# V9938.net
KiCad netlist of a schematic drawn in EAGLE
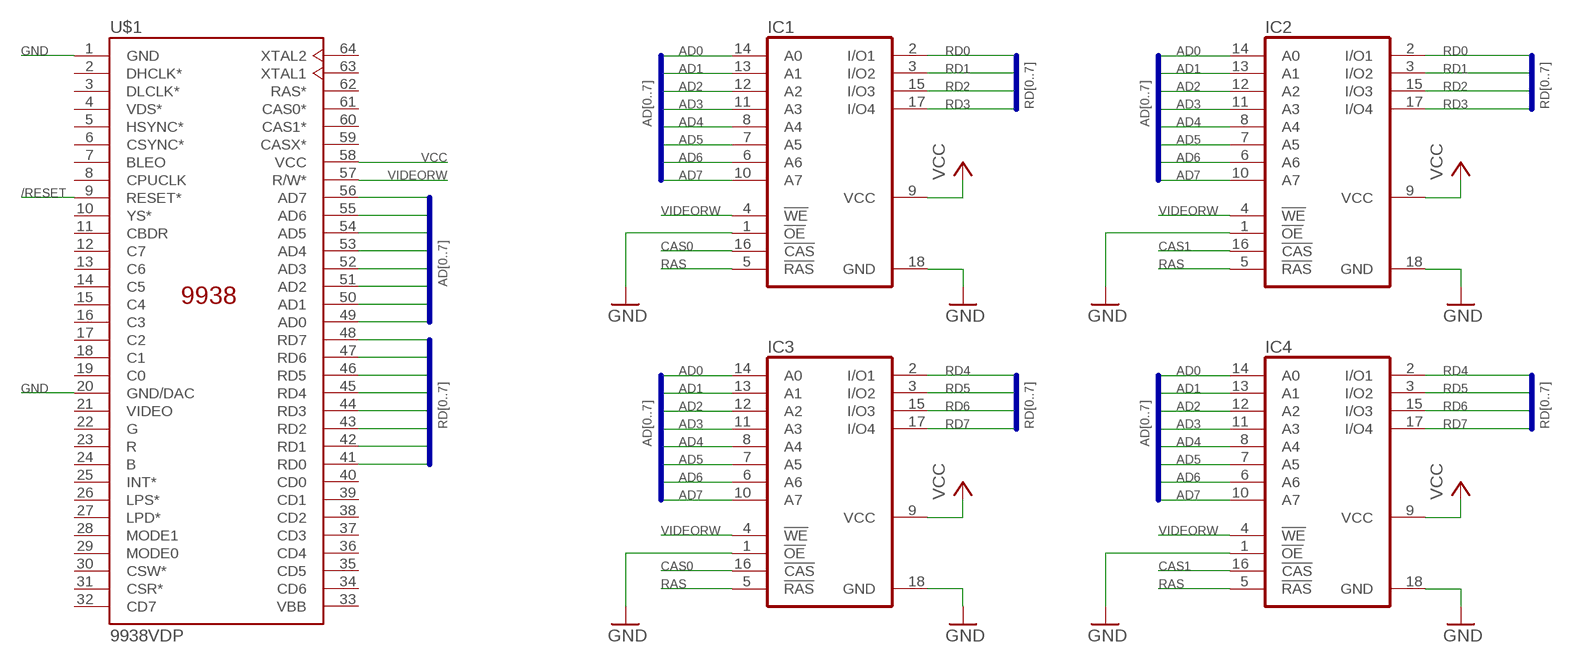
[diagram p0: schematic, sheet 1]

(export (version "E")
  (design (tool "Eeschema 10.0.6"))
  (components
    (comp (ref "IC1")
      (value "41464C")
      (footprint "eagle-import:DIL18")
      (libsource (lib "eagle-import") (part "41464C"))
    )
    (comp (ref "IC2")
      (value "41464C")
      (footprint "eagle-import:DIL18")
      (libsource (lib "eagle-import") (part "41464C"))
    )
    (comp (ref "IC3")
      (value "41464C")
      (footprint "eagle-import:DIL18")
      (libsource (lib "eagle-import") (part "41464C"))
    )
    (comp (ref "IC4")
      (value "41464C")
      (footprint "eagle-import:DIL18")
      (libsource (lib "eagle-import") (part "41464C"))
    )
    (comp (ref "U$1")
      (value "9938VDP")
      (footprint "eagle-import:DIL64-600")
      (libsource (lib "eagle-import") (part "9938VDP"))
    )
  )
  (nets
    (net (code "1") (name "/AD0") (class "Default")
      (node (ref "IC1") (pin "14") (pinfunction "A0_14") (pintype "input"))
      (node (ref "IC2") (pin "14") (pinfunction "A0_14") (pintype "input"))
      (node (ref "IC3") (pin "14") (pinfunction "A0_14") (pintype "input"))
      (node (ref "IC4") (pin "14") (pinfunction "A0_14") (pintype "input"))
      (node (ref "U$1") (pin "49") (pinfunction "AD0_49") (pintype "output"))
    )
    (net (code "2") (name "/AD1") (class "Default")
      (node (ref "IC1") (pin "13") (pinfunction "A1_13") (pintype "input"))
      (node (ref "IC2") (pin "13") (pinfunction "A1_13") (pintype "input"))
      (node (ref "IC3") (pin "13") (pinfunction "A1_13") (pintype "input"))
      (node (ref "IC4") (pin "13") (pinfunction "A1_13") (pintype "input"))
      (node (ref "U$1") (pin "50") (pinfunction "AD1_50") (pintype "output"))
    )
    (net (code "3") (name "/AD2") (class "Default")
      (node (ref "IC1") (pin "12") (pinfunction "A2_12") (pintype "input"))
      (node (ref "IC2") (pin "12") (pinfunction "A2_12") (pintype "input"))
      (node (ref "IC3") (pin "12") (pinfunction "A2_12") (pintype "input"))
      (node (ref "IC4") (pin "12") (pinfunction "A2_12") (pintype "input"))
      (node (ref "U$1") (pin "51") (pinfunction "AD2_51") (pintype "output"))
    )
    (net (code "4") (name "/AD3") (class "Default")
      (node (ref "IC1") (pin "11") (pinfunction "A3_11") (pintype "input"))
      (node (ref "IC2") (pin "11") (pinfunction "A3_11") (pintype "input"))
      (node (ref "IC3") (pin "11") (pinfunction "A3_11") (pintype "input"))
      (node (ref "IC4") (pin "11") (pinfunction "A3_11") (pintype "input"))
      (node (ref "U$1") (pin "52") (pinfunction "AD3_52") (pintype "output"))
    )
    (net (code "5") (name "/AD4") (class "Default")
      (node (ref "IC1") (pin "8") (pinfunction "A4_8") (pintype "input"))
      (node (ref "IC2") (pin "8") (pinfunction "A4_8") (pintype "input"))
      (node (ref "IC3") (pin "8") (pinfunction "A4_8") (pintype "input"))
      (node (ref "IC4") (pin "8") (pinfunction "A4_8") (pintype "input"))
      (node (ref "U$1") (pin "53") (pinfunction "AD4_53") (pintype "output"))
    )
    (net (code "6") (name "/AD5") (class "Default")
      (node (ref "IC1") (pin "7") (pinfunction "A5_7") (pintype "input"))
      (node (ref "IC2") (pin "7") (pinfunction "A5_7") (pintype "input"))
      (node (ref "IC3") (pin "7") (pinfunction "A5_7") (pintype "input"))
      (node (ref "IC4") (pin "7") (pinfunction "A5_7") (pintype "input"))
      (node (ref "U$1") (pin "54") (pinfunction "AD5_54") (pintype "output"))
    )
    (net (code "7") (name "/AD6") (class "Default")
      (node (ref "IC1") (pin "6") (pinfunction "A6_6") (pintype "input"))
      (node (ref "IC2") (pin "6") (pinfunction "A6_6") (pintype "input"))
      (node (ref "IC3") (pin "6") (pinfunction "A6_6") (pintype "input"))
      (node (ref "IC4") (pin "6") (pinfunction "A6_6") (pintype "input"))
      (node (ref "U$1") (pin "55") (pinfunction "AD6_55") (pintype "output"))
    )
    (net (code "8") (name "/AD7") (class "Default")
      (node (ref "IC1") (pin "10") (pinfunction "A7_10") (pintype "input"))
      (node (ref "IC2") (pin "10") (pinfunction "A7_10") (pintype "input"))
      (node (ref "IC3") (pin "10") (pinfunction "A7_10") (pintype "input"))
      (node (ref "IC4") (pin "10") (pinfunction "A7_10") (pintype "input"))
      (node (ref "U$1") (pin "56") (pinfunction "AD7_56") (pintype "output"))
    )
    (net (code "10") (name "/CAS0") (class "Default")
      (node (ref "IC1") (pin "16") (pinfunction "~{CAS}_16") (pintype "input"))
      (node (ref "IC3") (pin "16") (pinfunction "~{CAS}_16") (pintype "input"))
    )
    (net (code "11") (name "/CAS1") (class "Default")
      (node (ref "IC2") (pin "16") (pinfunction "~{CAS}_16") (pintype "input"))
      (node (ref "IC4") (pin "16") (pinfunction "~{CAS}_16") (pintype "input"))
    )
    (net (code "12") (name "/RAS") (class "Default")
      (node (ref "IC1") (pin "5") (pinfunction "~{RAS}_5") (pintype "input"))
      (node (ref "IC2") (pin "5") (pinfunction "~{RAS}_5") (pintype "input"))
      (node (ref "IC3") (pin "5") (pinfunction "~{RAS}_5") (pintype "input"))
      (node (ref "IC4") (pin "5") (pinfunction "~{RAS}_5") (pintype "input"))
    )
    (net (code "13") (name "/RD0") (class "Default")
      (node (ref "IC1") (pin "2") (pinfunction "I/O1_2") (pintype "bidirectional"))
      (node (ref "IC2") (pin "2") (pinfunction "I/O1_2") (pintype "bidirectional"))
      (node (ref "U$1") (pin "41") (pinfunction "RD0_41") (pintype "bidirectional"))
    )
    (net (code "14") (name "/RD1") (class "Default")
      (node (ref "IC1") (pin "3") (pinfunction "I/O2_3") (pintype "bidirectional"))
      (node (ref "IC2") (pin "3") (pinfunction "I/O2_3") (pintype "bidirectional"))
      (node (ref "U$1") (pin "42") (pinfunction "RD1_42") (pintype "bidirectional"))
    )
    (net (code "15") (name "/RD2") (class "Default")
      (node (ref "IC1") (pin "15") (pinfunction "I/O3_15") (pintype "bidirectional"))
      (node (ref "IC2") (pin "15") (pinfunction "I/O3_15") (pintype "bidirectional"))
      (node (ref "U$1") (pin "43") (pinfunction "RD2_43") (pintype "bidirectional"))
    )
    (net (code "16") (name "/RD3") (class "Default")
      (node (ref "IC1") (pin "17") (pinfunction "I/O4_17") (pintype "bidirectional"))
      (node (ref "IC2") (pin "17") (pinfunction "I/O4_17") (pintype "bidirectional"))
      (node (ref "U$1") (pin "44") (pinfunction "RD3_44") (pintype "bidirectional"))
    )
    (net (code "17") (name "/RD4") (class "Default")
      (node (ref "IC3") (pin "2") (pinfunction "I/O1_2") (pintype "bidirectional"))
      (node (ref "IC4") (pin "2") (pinfunction "I/O1_2") (pintype "bidirectional"))
      (node (ref "U$1") (pin "45") (pinfunction "RD4_45") (pintype "bidirectional"))
    )
    (net (code "18") (name "/RD5") (class "Default")
      (node (ref "IC3") (pin "3") (pinfunction "I/O2_3") (pintype "bidirectional"))
      (node (ref "IC4") (pin "3") (pinfunction "I/O2_3") (pintype "bidirectional"))
      (node (ref "U$1") (pin "46") (pinfunction "RD5_46") (pintype "bidirectional"))
    )
    (net (code "19") (name "/RD6") (class "Default")
      (node (ref "IC3") (pin "15") (pinfunction "I/O3_15") (pintype "bidirectional"))
      (node (ref "IC4") (pin "15") (pinfunction "I/O3_15") (pintype "bidirectional"))
      (node (ref "U$1") (pin "47") (pinfunction "RD6_47") (pintype "bidirectional"))
    )
    (net (code "20") (name "/RD7") (class "Default")
      (node (ref "IC3") (pin "17") (pinfunction "I/O4_17") (pintype "bidirectional"))
      (node (ref "IC4") (pin "17") (pinfunction "I/O4_17") (pintype "bidirectional"))
      (node (ref "U$1") (pin "48") (pinfunction "RD7_48") (pintype "bidirectional"))
    )
    (net (code "22") (name "/VIDEORW") (class "Default")
      (node (ref "IC1") (pin "4") (pinfunction "~{WE}_4") (pintype "input"))
      (node (ref "IC2") (pin "4") (pinfunction "~{WE}_4") (pintype "input"))
      (node (ref "IC3") (pin "4") (pinfunction "~{WE}_4") (pintype "input"))
      (node (ref "IC4") (pin "4") (pinfunction "~{WE}_4") (pintype "input"))
      (node (ref "U$1") (pin "57") (pinfunction "R/W*_57") (pintype "output"))
    )
    (net (code "23") (name "/{slash}RESET") (class "Default")
      (node (ref "U$1") (pin "9") (pinfunction "RESET*_9") (pintype "input"))
    )
    (net (code "24") (name "GND") (class "Default")
      (node (ref "IC1") (pin "1") (pinfunction "~{OE}_1") (pintype "input"))
      (node (ref "IC1") (pin "18") (pinfunction "GND_18") (pintype "power_in"))
      (node (ref "IC2") (pin "1") (pinfunction "~{OE}_1") (pintype "input"))
      (node (ref "IC2") (pin "18") (pinfunction "GND_18") (pintype "power_in"))
      (node (ref "IC3") (pin "1") (pinfunction "~{OE}_1") (pintype "input"))
      (node (ref "IC3") (pin "18") (pinfunction "GND_18") (pintype "power_in"))
      (node (ref "IC4") (pin "1") (pinfunction "~{OE}_1") (pintype "input"))
      (node (ref "IC4") (pin "18") (pinfunction "GND_18") (pintype "power_in"))
      (node (ref "U$1") (pin "1") (pinfunction "GND_1") (pintype "input"))
      (node (ref "U$1") (pin "20") (pinfunction "GND/DAC_20") (pintype "input"))
    )
    (net (code "25") (name "VCC") (class "Default")
      (node (ref "IC1") (pin "9") (pinfunction "VCC_9") (pintype "power_in"))
      (node (ref "IC2") (pin "9") (pinfunction "VCC_9") (pintype "power_in"))
      (node (ref "IC3") (pin "9") (pinfunction "VCC_9") (pintype "power_in"))
      (node (ref "IC4") (pin "9") (pinfunction "VCC_9") (pintype "power_in"))
      (node (ref "U$1") (pin "58") (pinfunction "VCC_58") (pintype "input"))
    )
    (net (code "26") (name "unconnected-(U$1-B-Pad24)") (class "Default")
      (node (ref "U$1") (pin "24") (pinfunction "B_24") (pintype "output"))
    )
    (net (code "27") (name "unconnected-(U$1-BLEO-Pad7)") (class "Default")
      (node (ref "U$1") (pin "7") (pinfunction "BLEO_7") (pintype "output"))
    )
    (net (code "28") (name "unconnected-(U$1-C0-Pad19)") (class "Default")
      (node (ref "U$1") (pin "19") (pinfunction "C0_19") (pintype "bidirectional"))
    )
    (net (code "29") (name "unconnected-(U$1-C1-Pad18)") (class "Default")
      (node (ref "U$1") (pin "18") (pinfunction "C1_18") (pintype "bidirectional"))
    )
    (net (code "30") (name "unconnected-(U$1-C2-Pad17)") (class "Default")
      (node (ref "U$1") (pin "17") (pinfunction "C2_17") (pintype "bidirectional"))
    )
    (net (code "31") (name "unconnected-(U$1-C3-Pad16)") (class "Default")
      (node (ref "U$1") (pin "16") (pinfunction "C3_16") (pintype "bidirectional"))
    )
    (net (code "32") (name "unconnected-(U$1-C4-Pad15)") (class "Default")
      (node (ref "U$1") (pin "15") (pinfunction "C4_15") (pintype "bidirectional"))
    )
    (net (code "33") (name "unconnected-(U$1-C5-Pad14)") (class "Default")
      (node (ref "U$1") (pin "14") (pinfunction "C5_14") (pintype "bidirectional"))
    )
    (net (code "34") (name "unconnected-(U$1-C6-Pad13)") (class "Default")
      (node (ref "U$1") (pin "13") (pinfunction "C6_13") (pintype "bidirectional"))
    )
    (net (code "35") (name "unconnected-(U$1-C7-Pad12)") (class "Default")
      (node (ref "U$1") (pin "12") (pinfunction "C7_12") (pintype "bidirectional"))
    )
    (net (code "36") (name "unconnected-(U$1-CAS0*-Pad61)") (class "Default")
      (node (ref "U$1") (pin "61") (pinfunction "CAS0*_61") (pintype "output"))
    )
    (net (code "37") (name "unconnected-(U$1-CAS1*-Pad60)") (class "Default")
      (node (ref "U$1") (pin "60") (pinfunction "CAS1*_60") (pintype "output"))
    )
    (net (code "38") (name "unconnected-(U$1-CASX*-Pad59)") (class "Default")
      (node (ref "U$1") (pin "59") (pinfunction "CASX*_59") (pintype "output"))
    )
    (net (code "39") (name "unconnected-(U$1-CBDR-Pad11)") (class "Default")
      (node (ref "U$1") (pin "11") (pinfunction "CBDR_11") (pintype "output"))
    )
    (net (code "40") (name "unconnected-(U$1-CD0-Pad40)") (class "Default")
      (node (ref "U$1") (pin "40") (pinfunction "CD0_40") (pintype "bidirectional"))
    )
    (net (code "41") (name "unconnected-(U$1-CD1-Pad39)") (class "Default")
      (node (ref "U$1") (pin "39") (pinfunction "CD1_39") (pintype "bidirectional"))
    )
    (net (code "42") (name "unconnected-(U$1-CD2-Pad38)") (class "Default")
      (node (ref "U$1") (pin "38") (pinfunction "CD2_38") (pintype "bidirectional"))
    )
    (net (code "43") (name "unconnected-(U$1-CD3-Pad37)") (class "Default")
      (node (ref "U$1") (pin "37") (pinfunction "CD3_37") (pintype "bidirectional"))
    )
    (net (code "44") (name "unconnected-(U$1-CD4-Pad36)") (class "Default")
      (node (ref "U$1") (pin "36") (pinfunction "CD4_36") (pintype "bidirectional"))
    )
    (net (code "45") (name "unconnected-(U$1-CD5-Pad35)") (class "Default")
      (node (ref "U$1") (pin "35") (pinfunction "CD5_35") (pintype "bidirectional"))
    )
    (net (code "46") (name "unconnected-(U$1-CD6-Pad34)") (class "Default")
      (node (ref "U$1") (pin "34") (pinfunction "CD6_34") (pintype "bidirectional"))
    )
    (net (code "47") (name "unconnected-(U$1-CD7-Pad32)") (class "Default")
      (node (ref "U$1") (pin "32") (pinfunction "CD7_32") (pintype "bidirectional"))
    )
    (net (code "48") (name "unconnected-(U$1-CPUCLK-Pad8)") (class "Default")
      (node (ref "U$1") (pin "8") (pinfunction "CPUCLK_8") (pintype "output"))
    )
    (net (code "49") (name "unconnected-(U$1-CSR*-Pad31)") (class "Default")
      (node (ref "U$1") (pin "31") (pinfunction "CSR*_31") (pintype "input"))
    )
    (net (code "50") (name "unconnected-(U$1-CSW*-Pad30)") (class "Default")
      (node (ref "U$1") (pin "30") (pinfunction "CSW*_30") (pintype "input"))
    )
    (net (code "51") (name "unconnected-(U$1-CSYNC*-Pad6)") (class "Default")
      (node (ref "U$1") (pin "6") (pinfunction "CSYNC*_6") (pintype "bidirectional"))
    )
    (net (code "52") (name "unconnected-(U$1-DHCLK*-Pad2)") (class "Default")
      (node (ref "U$1") (pin "2") (pinfunction "DHCLK*_2") (pintype "output"))
    )
    (net (code "53") (name "unconnected-(U$1-DLCLK*-Pad3)") (class "Default")
      (node (ref "U$1") (pin "3") (pinfunction "DLCLK*_3") (pintype "bidirectional"))
    )
    (net (code "54") (name "unconnected-(U$1-G-Pad22)") (class "Default")
      (node (ref "U$1") (pin "22") (pinfunction "G_22") (pintype "output"))
    )
    (net (code "55") (name "unconnected-(U$1-HSYNC*-Pad5)") (class "Default")
      (node (ref "U$1") (pin "5") (pinfunction "HSYNC*_5") (pintype "bidirectional"))
    )
    (net (code "56") (name "unconnected-(U$1-INT*-Pad25)") (class "Default")
      (node (ref "U$1") (pin "25") (pinfunction "INT*_25") (pintype "output"))
    )
    (net (code "57") (name "unconnected-(U$1-LPD*-Pad27)") (class "Default")
      (node (ref "U$1") (pin "27") (pinfunction "LPD*_27") (pintype "input"))
    )
    (net (code "58") (name "unconnected-(U$1-LPS*-Pad26)") (class "Default")
      (node (ref "U$1") (pin "26") (pinfunction "LPS*_26") (pintype "input"))
    )
    (net (code "59") (name "unconnected-(U$1-MODE0-Pad29)") (class "Default")
      (node (ref "U$1") (pin "29") (pinfunction "MODE0_29") (pintype "input"))
    )
    (net (code "60") (name "unconnected-(U$1-MODE1-Pad28)") (class "Default")
      (node (ref "U$1") (pin "28") (pinfunction "MODE1_28") (pintype "input"))
    )
    (net (code "61") (name "unconnected-(U$1-R-Pad23)") (class "Default")
      (node (ref "U$1") (pin "23") (pinfunction "R_23") (pintype "output"))
    )
    (net (code "62") (name "unconnected-(U$1-RAS*-Pad62)") (class "Default")
      (node (ref "U$1") (pin "62") (pinfunction "RAS*_62") (pintype "output"))
    )
    (net (code "63") (name "unconnected-(U$1-VBB-Pad33)") (class "Default")
      (node (ref "U$1") (pin "33") (pinfunction "VBB_33") (pintype "output"))
    )
    (net (code "64") (name "unconnected-(U$1-VDS*-Pad4)") (class "Default")
      (node (ref "U$1") (pin "4") (pinfunction "VDS*_4") (pintype "output"))
    )
    (net (code "65") (name "unconnected-(U$1-VIDEO-Pad21)") (class "Default")
      (node (ref "U$1") (pin "21") (pinfunction "VIDEO_21") (pintype "output"))
    )
    (net (code "66") (name "unconnected-(U$1-XTAL1-Pad63)") (class "Default")
      (node (ref "U$1") (pin "63") (pinfunction "XTAL1_63") (pintype "input"))
    )
    (net (code "67") (name "unconnected-(U$1-XTAL2-Pad64)") (class "Default")
      (node (ref "U$1") (pin "64") (pinfunction "XTAL2_64") (pintype "input"))
    )
    (net (code "68") (name "unconnected-(U$1-YS*-Pad10)") (class "Default")
      (node (ref "U$1") (pin "10") (pinfunction "YS*_10") (pintype "output"))
    )
  )
)
